# untitled.net
KiCad netlist of a schematic drawn in EAGLE
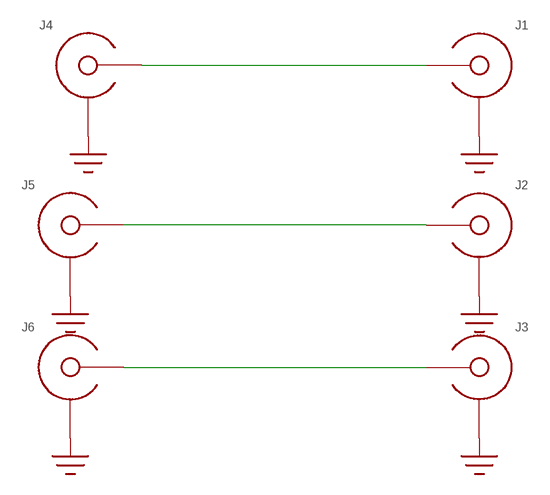
[diagram p0: schematic, sheet 1]

(export (version "E")
  (design (tool "Eeschema 10.0.6"))
  (components
    (comp (ref "J1")
      (value "SMA-EDGE-LAUNCH4020_TAPER")
      (footprint "eagle-import:SMA_EDGE_LAUNCH_2L_4020_TAPER")
      (libsource (lib "eagle-import") (part "SMA-EDGE-LAUNCH4020_TAPER"))
    )
    (comp (ref "J2")
      (value "SMA-EDGE-LAUNCH4L-4020-TAPER-FIXED")
      (footprint "eagle-import:SMA_EDGE_LAUNCH_4L_4020_TAPER_FIXED")
      (libsource (lib "eagle-import") (part "SMA-EDGE-LAUNCH4L-4020-TAPER-FIXED"))
    )
    (comp (ref "J3")
      (value "SMA-EDGE-LAUNCHCUT-PIN")
      (footprint "eagle-import:SMA_EDGE_LAUNCH_2L_4020_CUT_PIN")
      (libsource (lib "eagle-import") (part "SMA-EDGE-LAUNCHCUT-PIN"))
    )
    (comp (ref "J4")
      (value "SMA-EDGE-LAUNCH4020_TAPER")
      (footprint "eagle-import:SMA_EDGE_LAUNCH_2L_4020_TAPER")
      (libsource (lib "eagle-import") (part "SMA-EDGE-LAUNCH4020_TAPER"))
    )
    (comp (ref "J5")
      (value "SMA-EDGE-LAUNCH4L-4020-TAPER-FIXED")
      (footprint "eagle-import:SMA_EDGE_LAUNCH_4L_4020_TAPER_FIXED")
      (libsource (lib "eagle-import") (part "SMA-EDGE-LAUNCH4L-4020-TAPER-FIXED"))
    )
    (comp (ref "J6")
      (value "SMA-EDGE-LAUNCHCUT-PIN")
      (footprint "eagle-import:SMA_EDGE_LAUNCH_2L_4020_CUT_PIN")
      (libsource (lib "eagle-import") (part "SMA-EDGE-LAUNCHCUT-PIN"))
    )
  )
  (nets
    (net (code "1") (name "GND") (class "Default")
      (node (ref "J1") (pin "BOTTOM_GND") (pinfunction "SHIELD_BOTTOM_GND") (pintype "bidirectional"))
      (node (ref "J1") (pin "GND@1") (pinfunction "SHIELD_GND@1") (pintype "bidirectional"))
      (node (ref "J1") (pin "GND@14") (pinfunction "SHIELD_GND@14") (pintype "bidirectional"))
      (node (ref "J1") (pin "GND@15") (pinfunction "SHIELD_GND@15") (pintype "bidirectional"))
      (node (ref "J1") (pin "GND@16") (pinfunction "SHIELD_GND@16") (pintype "bidirectional"))
      (node (ref "J1") (pin "GND@17") (pinfunction "SHIELD_GND@17") (pintype "bidirectional"))
      (node (ref "J1") (pin "GND@2") (pinfunction "SHIELD_GND@2") (pintype "bidirectional"))
      (node (ref "J1") (pin "GND@3") (pinfunction "SHIELD_GND@3") (pintype "bidirectional"))
      (node (ref "J1") (pin "GND@4") (pinfunction "SHIELD_GND@4") (pintype "bidirectional"))
      (node (ref "J1") (pin "GND@5") (pinfunction "SHIELD_GND@5") (pintype "bidirectional"))
      (node (ref "J1") (pin "GND@6") (pinfunction "SHIELD_GND@6") (pintype "bidirectional"))
      (node (ref "J1") (pin "GND@7") (pinfunction "SHIELD_GND@7") (pintype "bidirectional"))
      (node (ref "J1") (pin "GND@8") (pinfunction "SHIELD_GND@8") (pintype "bidirectional"))
      (node (ref "J1") (pin "GND_PAD1") (pinfunction "SHIELD_GND_PAD1") (pintype "bidirectional"))
      (node (ref "J1") (pin "GND_PAD2") (pinfunction "SHIELD_GND_PAD2") (pintype "bidirectional"))
      (node (ref "J1") (pin "P$1") (pinfunction "SHIELD_P$1") (pintype "bidirectional"))
      (node (ref "J1") (pin "P$2") (pinfunction "SHIELD_P$2") (pintype "bidirectional"))
      (node (ref "J2") (pin "BOTTOM_GND") (pinfunction "SHIELD_BOTTOM_GND") (pintype "bidirectional"))
      (node (ref "J2") (pin "GND@1") (pinfunction "SHIELD_GND@1") (pintype "bidirectional"))
      (node (ref "J2") (pin "GND@14") (pinfunction "SHIELD_GND@14") (pintype "bidirectional"))
      (node (ref "J2") (pin "GND@15") (pinfunction "SHIELD_GND@15") (pintype "bidirectional"))
      (node (ref "J2") (pin "GND@16") (pinfunction "SHIELD_GND@16") (pintype "bidirectional"))
      (node (ref "J2") (pin "GND@17") (pinfunction "SHIELD_GND@17") (pintype "bidirectional"))
      (node (ref "J2") (pin "GND@2") (pinfunction "SHIELD_GND@2") (pintype "bidirectional"))
      (node (ref "J2") (pin "GND@3") (pinfunction "SHIELD_GND@3") (pintype "bidirectional"))
      (node (ref "J2") (pin "GND@4") (pinfunction "SHIELD_GND@4") (pintype "bidirectional"))
      (node (ref "J2") (pin "GND@5") (pinfunction "SHIELD_GND@5") (pintype "bidirectional"))
      (node (ref "J2") (pin "GND@6") (pinfunction "SHIELD_GND@6") (pintype "bidirectional"))
      (node (ref "J2") (pin "GND@7") (pinfunction "SHIELD_GND@7") (pintype "bidirectional"))
      (node (ref "J2") (pin "GND@8") (pinfunction "SHIELD_GND@8") (pintype "bidirectional"))
      (node (ref "J2") (pin "GND_PAD1") (pinfunction "SHIELD_GND_PAD1") (pintype "bidirectional"))
      (node (ref "J2") (pin "GND_PAD2") (pinfunction "SHIELD_GND_PAD2") (pintype "bidirectional"))
      (node (ref "J2") (pin "P$1") (pinfunction "SHIELD_P$1") (pintype "bidirectional"))
      (node (ref "J2") (pin "P$2") (pinfunction "SHIELD_P$2") (pintype "bidirectional"))
      (node (ref "J3") (pin "BOTTOM_GND") (pinfunction "SHIELD_BOTTOM_GND") (pintype "bidirectional"))
      (node (ref "J3") (pin "GND@1") (pinfunction "SHIELD_GND@1") (pintype "bidirectional"))
      (node (ref "J3") (pin "GND@14") (pinfunction "SHIELD_GND@14") (pintype "bidirectional"))
      (node (ref "J3") (pin "GND@15") (pinfunction "SHIELD_GND@15") (pintype "bidirectional"))
      (node (ref "J3") (pin "GND@16") (pinfunction "SHIELD_GND@16") (pintype "bidirectional"))
      (node (ref "J3") (pin "GND@17") (pinfunction "SHIELD_GND@17") (pintype "bidirectional"))
      (node (ref "J3") (pin "GND@2") (pinfunction "SHIELD_GND@2") (pintype "bidirectional"))
      (node (ref "J3") (pin "GND@3") (pinfunction "SHIELD_GND@3") (pintype "bidirectional"))
      (node (ref "J3") (pin "GND@4") (pinfunction "SHIELD_GND@4") (pintype "bidirectional"))
      (node (ref "J3") (pin "GND@5") (pinfunction "SHIELD_GND@5") (pintype "bidirectional"))
      (node (ref "J3") (pin "GND@6") (pinfunction "SHIELD_GND@6") (pintype "bidirectional"))
      (node (ref "J3") (pin "GND@7") (pinfunction "SHIELD_GND@7") (pintype "bidirectional"))
      (node (ref "J3") (pin "GND@8") (pinfunction "SHIELD_GND@8") (pintype "bidirectional"))
      (node (ref "J3") (pin "GND_PAD1") (pinfunction "SHIELD_GND_PAD1") (pintype "bidirectional"))
      (node (ref "J3") (pin "GND_PAD2") (pinfunction "SHIELD_GND_PAD2") (pintype "bidirectional"))
      (node (ref "J4") (pin "BOTTOM_GND") (pinfunction "SHIELD_BOTTOM_GND") (pintype "bidirectional"))
      (node (ref "J4") (pin "GND@1") (pinfunction "SHIELD_GND@1") (pintype "bidirectional"))
      (node (ref "J4") (pin "GND@14") (pinfunction "SHIELD_GND@14") (pintype "bidirectional"))
      (node (ref "J4") (pin "GND@15") (pinfunction "SHIELD_GND@15") (pintype "bidirectional"))
      (node (ref "J4") (pin "GND@16") (pinfunction "SHIELD_GND@16") (pintype "bidirectional"))
      (node (ref "J4") (pin "GND@17") (pinfunction "SHIELD_GND@17") (pintype "bidirectional"))
      (node (ref "J4") (pin "GND@2") (pinfunction "SHIELD_GND@2") (pintype "bidirectional"))
      (node (ref "J4") (pin "GND@3") (pinfunction "SHIELD_GND@3") (pintype "bidirectional"))
      (node (ref "J4") (pin "GND@4") (pinfunction "SHIELD_GND@4") (pintype "bidirectional"))
      (node (ref "J4") (pin "GND@5") (pinfunction "SHIELD_GND@5") (pintype "bidirectional"))
      (node (ref "J4") (pin "GND@6") (pinfunction "SHIELD_GND@6") (pintype "bidirectional"))
      (node (ref "J4") (pin "GND@7") (pinfunction "SHIELD_GND@7") (pintype "bidirectional"))
      (node (ref "J4") (pin "GND@8") (pinfunction "SHIELD_GND@8") (pintype "bidirectional"))
      (node (ref "J4") (pin "GND_PAD1") (pinfunction "SHIELD_GND_PAD1") (pintype "bidirectional"))
      (node (ref "J4") (pin "GND_PAD2") (pinfunction "SHIELD_GND_PAD2") (pintype "bidirectional"))
      (node (ref "J4") (pin "P$1") (pinfunction "SHIELD_P$1") (pintype "bidirectional"))
      (node (ref "J4") (pin "P$2") (pinfunction "SHIELD_P$2") (pintype "bidirectional"))
      (node (ref "J5") (pin "BOTTOM_GND") (pinfunction "SHIELD_BOTTOM_GND") (pintype "bidirectional"))
      (node (ref "J5") (pin "GND@1") (pinfunction "SHIELD_GND@1") (pintype "bidirectional"))
      (node (ref "J5") (pin "GND@14") (pinfunction "SHIELD_GND@14") (pintype "bidirectional"))
      (node (ref "J5") (pin "GND@15") (pinfunction "SHIELD_GND@15") (pintype "bidirectional"))
      (node (ref "J5") (pin "GND@16") (pinfunction "SHIELD_GND@16") (pintype "bidirectional"))
      (node (ref "J5") (pin "GND@17") (pinfunction "SHIELD_GND@17") (pintype "bidirectional"))
      (node (ref "J5") (pin "GND@2") (pinfunction "SHIELD_GND@2") (pintype "bidirectional"))
      (node (ref "J5") (pin "GND@3") (pinfunction "SHIELD_GND@3") (pintype "bidirectional"))
      (node (ref "J5") (pin "GND@4") (pinfunction "SHIELD_GND@4") (pintype "bidirectional"))
      (node (ref "J5") (pin "GND@5") (pinfunction "SHIELD_GND@5") (pintype "bidirectional"))
      (node (ref "J5") (pin "GND@6") (pinfunction "SHIELD_GND@6") (pintype "bidirectional"))
      (node (ref "J5") (pin "GND@7") (pinfunction "SHIELD_GND@7") (pintype "bidirectional"))
      (node (ref "J5") (pin "GND@8") (pinfunction "SHIELD_GND@8") (pintype "bidirectional"))
      (node (ref "J5") (pin "GND_PAD1") (pinfunction "SHIELD_GND_PAD1") (pintype "bidirectional"))
      (node (ref "J5") (pin "GND_PAD2") (pinfunction "SHIELD_GND_PAD2") (pintype "bidirectional"))
      (node (ref "J5") (pin "P$1") (pinfunction "SHIELD_P$1") (pintype "bidirectional"))
      (node (ref "J5") (pin "P$2") (pinfunction "SHIELD_P$2") (pintype "bidirectional"))
      (node (ref "J6") (pin "BOTTOM_GND") (pinfunction "SHIELD_BOTTOM_GND") (pintype "bidirectional"))
      (node (ref "J6") (pin "GND@1") (pinfunction "SHIELD_GND@1") (pintype "bidirectional"))
      (node (ref "J6") (pin "GND@14") (pinfunction "SHIELD_GND@14") (pintype "bidirectional"))
      (node (ref "J6") (pin "GND@15") (pinfunction "SHIELD_GND@15") (pintype "bidirectional"))
      (node (ref "J6") (pin "GND@16") (pinfunction "SHIELD_GND@16") (pintype "bidirectional"))
      (node (ref "J6") (pin "GND@17") (pinfunction "SHIELD_GND@17") (pintype "bidirectional"))
      (node (ref "J6") (pin "GND@2") (pinfunction "SHIELD_GND@2") (pintype "bidirectional"))
      (node (ref "J6") (pin "GND@3") (pinfunction "SHIELD_GND@3") (pintype "bidirectional"))
      (node (ref "J6") (pin "GND@4") (pinfunction "SHIELD_GND@4") (pintype "bidirectional"))
      (node (ref "J6") (pin "GND@5") (pinfunction "SHIELD_GND@5") (pintype "bidirectional"))
      (node (ref "J6") (pin "GND@6") (pinfunction "SHIELD_GND@6") (pintype "bidirectional"))
      (node (ref "J6") (pin "GND@7") (pinfunction "SHIELD_GND@7") (pintype "bidirectional"))
      (node (ref "J6") (pin "GND@8") (pinfunction "SHIELD_GND@8") (pintype "bidirectional"))
      (node (ref "J6") (pin "GND_PAD1") (pinfunction "SHIELD_GND_PAD1") (pintype "bidirectional"))
      (node (ref "J6") (pin "GND_PAD2") (pinfunction "SHIELD_GND_PAD2") (pintype "bidirectional"))
    )
    (net (code "2") (name "Net-(J1-CENTER)") (class "Default")
      (node (ref "J1") (pin "CENTER@1") (pinfunction "CENTER_CENTER@1") (pintype "bidirectional"))
      (node (ref "J4") (pin "CENTER@1") (pinfunction "CENTER_CENTER@1") (pintype "bidirectional"))
    )
    (net (code "3") (name "Net-(J2-CENTER-PadCENTER@1)") (class "Default")
      (node (ref "J2") (pin "CENTER@1") (pinfunction "CENTER_CENTER@1") (pintype "bidirectional"))
      (node (ref "J2") (pin "P$3") (pinfunction "CENTER_P$3") (pintype "bidirectional"))
      (node (ref "J5") (pin "CENTER@1") (pinfunction "CENTER_CENTER@1") (pintype "bidirectional"))
      (node (ref "J5") (pin "P$3") (pinfunction "CENTER_P$3") (pintype "bidirectional"))
    )
    (net (code "4") (name "Net-(J3-CENTER-PadCENTER@1)") (class "Default")
      (node (ref "J3") (pin "CENTER@1") (pinfunction "CENTER_CENTER@1") (pintype "bidirectional"))
      (node (ref "J3") (pin "CENTER@3") (pinfunction "CENTER_CENTER@3") (pintype "bidirectional"))
      (node (ref "J6") (pin "CENTER@1") (pinfunction "CENTER_CENTER@1") (pintype "bidirectional"))
      (node (ref "J6") (pin "CENTER@3") (pinfunction "CENTER_CENTER@3") (pintype "bidirectional"))
    )
  )
)
